# connector.net
KiCad netlist of a schematic drawn in Altium Designer
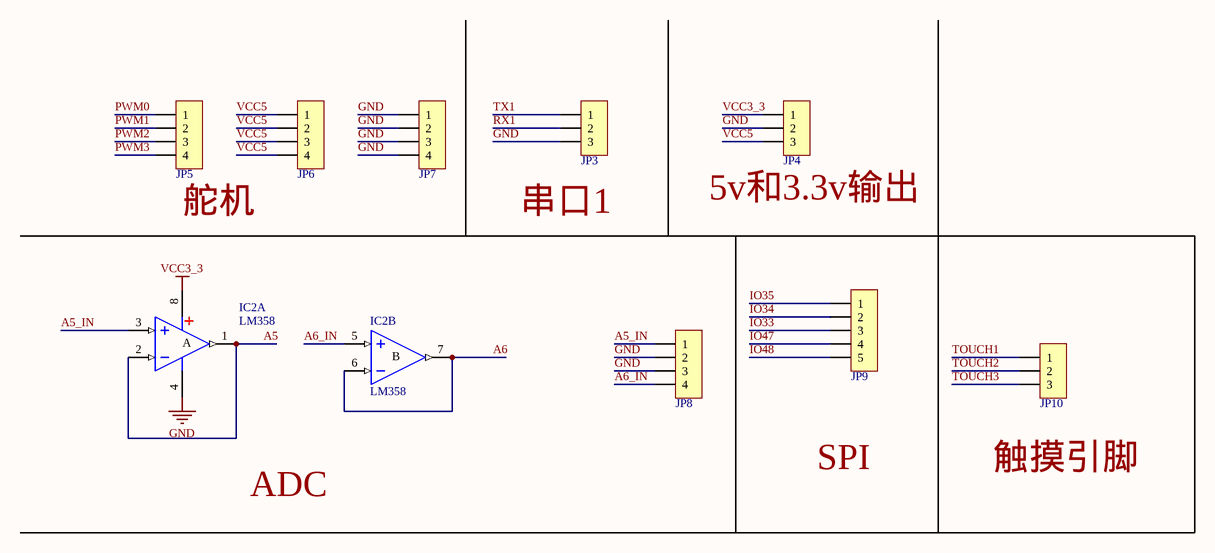
[diagram p0: connector.SchDoc]

(export (version "E")
  (design (tool "Eeschema 10.0.6"))
  (components
    (comp (ref "IC2")
      (value "LM358")
      (footprint "SOP8_N")
      (description "双路运放")
      (libsource (lib "0.8 - 常见芯片") (part "LM358"))
    )
    (comp (ref "JP3")
      (value "HDR-1X3")
      (footprint "HDR2.54-LI-3P")
      (description "3P接插件")
      (libsource (lib "5.5 - 2.54mm连接器(KF2EDGK_XH2.54_2.54排针排母)") (part "Header 3"))
    )
    (comp (ref "JP4")
      (value "HDR-1X3")
      (footprint "HDR2.54-LI-3P")
      (description "3P接插件")
      (libsource (lib "5.5 - 2.54mm连接器(KF2EDGK_XH2.54_2.54排针排母)") (part "Header 3"))
    )
    (comp (ref "JP5")
      (value "HDR-1X4")
      (footprint "HDR2.54-LI-4P")
      (description "4P接插件")
      (libsource (lib "5.5 - 2.54mm连接器(KF2EDGK_XH2.54_2.54排针排母)") (part "Header 4"))
    )
    (comp (ref "JP6")
      (value "HDR-1X4")
      (footprint "HDR2.54-LI-4P")
      (description "4P接插件")
      (libsource (lib "5.5 - 2.54mm连接器(KF2EDGK_XH2.54_2.54排针排母)") (part "Header 4"))
    )
    (comp (ref "JP7")
      (value "HDR-1X4")
      (footprint "HDR2.54-LI-4P")
      (description "4P接插件")
      (libsource (lib "5.5 - 2.54mm连接器(KF2EDGK_XH2.54_2.54排针排母)") (part "Header 4"))
    )
    (comp (ref "JP8")
      (value "HDR-1X4")
      (footprint "HDR2.54-LI-4P")
      (description "4P接插件")
      (libsource (lib "5.5 - 2.54mm连接器(KF2EDGK_XH2.54_2.54排针排母)") (part "Header 4"))
    )
    (comp (ref "JP9")
      (value "HDR-1X5")
      (footprint "HDR2.54-LI-5P")
      (description "5P接插件")
      (libsource (lib "5.5 - 2.54mm连接器(KF2EDGK_XH2.54_2.54排针排母)") (part "Header 5"))
    )
    (comp (ref "JP10")
      (value "HDR-1X3")
      (footprint "HDR2.54-LI-3P")
      (description "3P接插件")
      (libsource (lib "5.5 - 2.54mm连接器(KF2EDGK_XH2.54_2.54排针排母)") (part "Header 3"))
    )
  )
  (nets
    (net (code "1") (name "/A5") (class "Default")
      (node (ref "IC2") (pin "1") (pinfunction "OUT_1") (pintype "output"))
      (node (ref "IC2") (pin "2") (pinfunction "IN-_2") (pintype "input"))
    )
    (net (code "2") (name "/A5_IN") (class "Default")
      (node (ref "IC2") (pin "3") (pinfunction "IN+_3") (pintype "input"))
      (node (ref "JP8") (pin "1") (pinfunction "1_1") (pintype "passive"))
    )
    (net (code "3") (name "/A6") (class "Default")
      (node (ref "IC2") (pin "6") (pinfunction "IN-_6") (pintype "input"))
      (node (ref "IC2") (pin "7") (pinfunction "OUT_7") (pintype "output"))
    )
    (net (code "4") (name "/A6_IN") (class "Default")
      (node (ref "IC2") (pin "5") (pinfunction "IN+_5") (pintype "input"))
      (node (ref "JP8") (pin "4") (pinfunction "4_4") (pintype "passive"))
    )
    (net (code "5") (name "/IO33") (class "Default")
      (node (ref "JP9") (pin "3") (pinfunction "3_3") (pintype "passive"))
    )
    (net (code "6") (name "/IO34") (class "Default")
      (node (ref "JP9") (pin "2") (pinfunction "2_2") (pintype "passive"))
    )
    (net (code "7") (name "/IO35") (class "Default")
      (node (ref "JP9") (pin "1") (pinfunction "1_1") (pintype "passive"))
    )
    (net (code "8") (name "/IO47") (class "Default")
      (node (ref "JP9") (pin "4") (pinfunction "4_4") (pintype "passive"))
    )
    (net (code "9") (name "/IO48") (class "Default")
      (node (ref "JP9") (pin "5") (pinfunction "5_5") (pintype "passive"))
    )
    (net (code "10") (name "/PWM0") (class "Default")
      (node (ref "JP5") (pin "1") (pinfunction "1_1") (pintype "passive"))
    )
    (net (code "11") (name "/PWM1") (class "Default")
      (node (ref "JP5") (pin "2") (pinfunction "2_2") (pintype "passive"))
    )
    (net (code "12") (name "/PWM2") (class "Default")
      (node (ref "JP5") (pin "3") (pinfunction "3_3") (pintype "passive"))
    )
    (net (code "13") (name "/PWM3") (class "Default")
      (node (ref "JP5") (pin "4") (pinfunction "4_4") (pintype "passive"))
    )
    (net (code "14") (name "/RX1") (class "Default")
      (node (ref "JP3") (pin "2") (pinfunction "2_2") (pintype "passive"))
    )
    (net (code "15") (name "/TOUCH1") (class "Default")
      (node (ref "JP10") (pin "1") (pinfunction "1_1") (pintype "passive"))
    )
    (net (code "16") (name "/TOUCH2") (class "Default")
      (node (ref "JP10") (pin "2") (pinfunction "2_2") (pintype "passive"))
    )
    (net (code "17") (name "/TOUCH3") (class "Default")
      (node (ref "JP10") (pin "3") (pinfunction "3_3") (pintype "passive"))
    )
    (net (code "18") (name "/TX1") (class "Default")
      (node (ref "JP3") (pin "1") (pinfunction "1_1") (pintype "passive"))
    )
    (net (code "19") (name "/VCC5") (class "Default")
      (node (ref "JP4") (pin "3") (pinfunction "3_3") (pintype "passive"))
      (node (ref "JP6") (pin "1") (pinfunction "1_1") (pintype "passive"))
      (node (ref "JP6") (pin "2") (pinfunction "2_2") (pintype "passive"))
      (node (ref "JP6") (pin "3") (pinfunction "3_3") (pintype "passive"))
      (node (ref "JP6") (pin "4") (pinfunction "4_4") (pintype "passive"))
    )
    (net (code "20") (name "GND") (class "Default")
      (node (ref "IC2") (pin "4") (pinfunction "V-_4") (pintype "power_in"))
      (node (ref "JP3") (pin "3") (pinfunction "3_3") (pintype "passive"))
      (node (ref "JP4") (pin "2") (pinfunction "2_2") (pintype "passive"))
      (node (ref "JP7") (pin "1") (pinfunction "1_1") (pintype "passive"))
      (node (ref "JP7") (pin "2") (pinfunction "2_2") (pintype "passive"))
      (node (ref "JP7") (pin "3") (pinfunction "3_3") (pintype "passive"))
      (node (ref "JP7") (pin "4") (pinfunction "4_4") (pintype "passive"))
      (node (ref "JP8") (pin "2") (pinfunction "2_2") (pintype "passive"))
      (node (ref "JP8") (pin "3") (pinfunction "3_3") (pintype "passive"))
    )
    (net (code "21") (name "VCC3_3") (class "Default")
      (node (ref "IC2") (pin "8") (pinfunction "V+_8") (pintype "power_in"))
      (node (ref "JP4") (pin "1") (pinfunction "1_1") (pintype "passive"))
    )
  )
)
